# Brickster_8884bt_Receiver.net
KiCad netlist of a schematic drawn in EAGLE
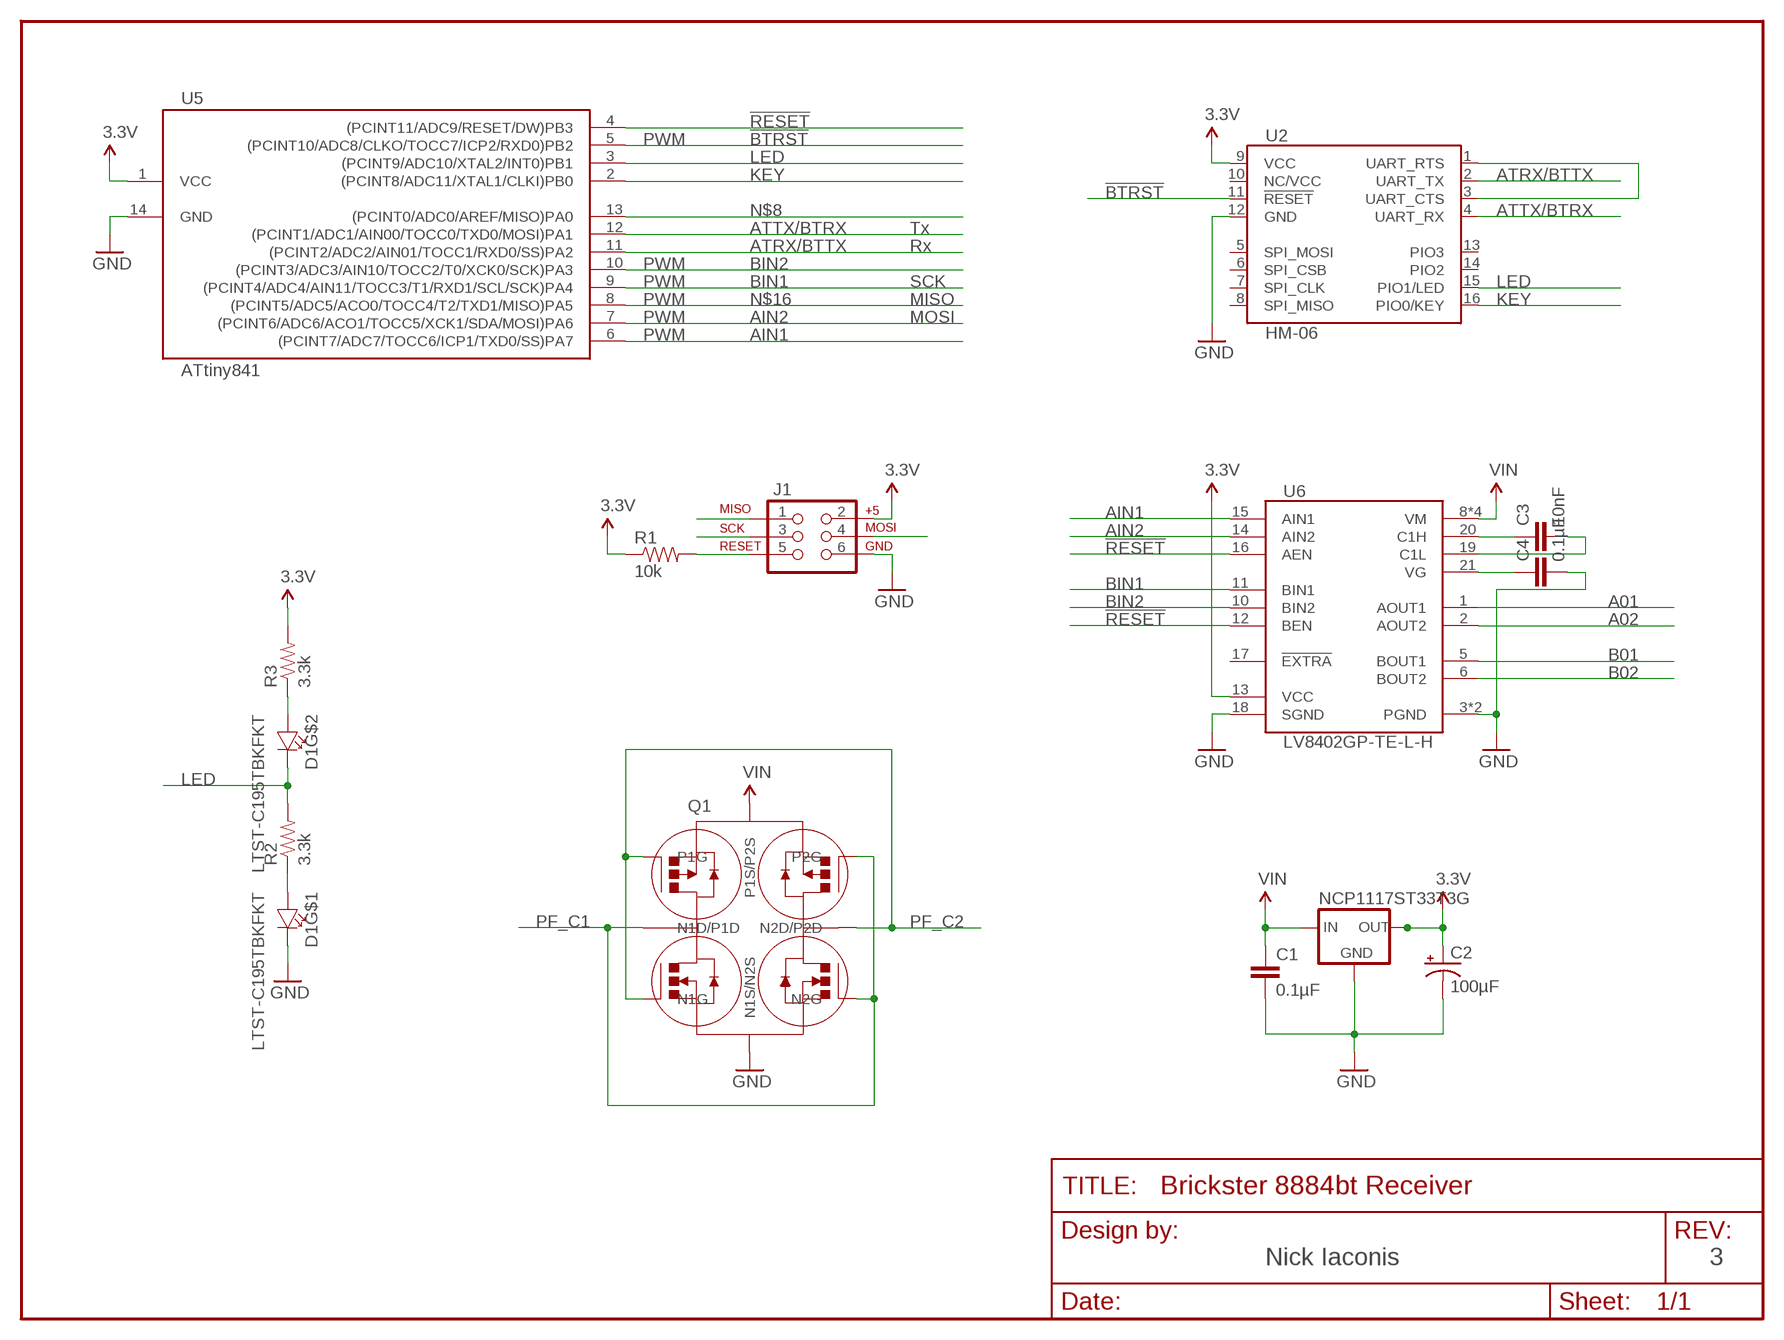
[diagram p0: schematic, sheet 1]

(export (version "E")
  (design (tool "Eeschema 10.0.6"))
  (components
    (comp (ref "C1")
      (value "0.1µF")
      (footprint "eagle-import:0402")
      (libsource (lib "eagle-import") (part "C0402"))
    )
    (comp (ref "C2")
      (value "100µF")
      (footprint "eagle-import:1206")
      (libsource (lib "eagle-import") (part "C_POL"))
    )
    (comp (ref "C3")
      (value "10nF")
      (footprint "eagle-import:0402")
      (libsource (lib "eagle-import") (part "C0402"))
    )
    (comp (ref "C4")
      (value "0.1µF")
      (footprint "eagle-import:0402")
      (libsource (lib "eagle-import") (part "C0402"))
    )
    (comp (ref "D1")
      (value "LTST-C195TBKFKT")
      (footprint "eagle-import:CHIP-LTST")
      (libsource (lib "eagle-import") (part "LED_LTST_C195TBKFKT"))
    )
    (comp (ref "J1")
      (value "AVR_SPI_PRG_6NS")
      (footprint "eagle-import:2X3-NS")
      (libsource (lib "eagle-import") (part "AVR_SPI_PRG_6NS"))
    )
    (comp (ref "NCP1117ST33T3G")
      (value "IC_RT9164A")
      (footprint "eagle-import:SOT223")
      (libsource (lib "eagle-import") (part "IC_RT9164A"))
    )
    (comp (ref "Q1")
      (value "DMHC3025LSD-13")
      (footprint "eagle-import:SO8")
      (libsource (lib "eagle-import") (part "IC_FET_BRIDGESO8"))
    )
    (comp (ref "R1")
      (value "10k")
      (footprint "eagle-import:0402")
      (fields (field (name "PARTNO") "ERJ-3GEYJ103V"))
      (libsource (lib "eagle-import") (part "R0402"))
    )
    (comp (ref "R2")
      (value "3.3k")
      (footprint "eagle-import:0402")
      (fields (field (name "PARTNO") "ERJ-3GEYJ103V"))
      (libsource (lib "eagle-import") (part "R0402"))
    )
    (comp (ref "R3")
      (value "3.3k")
      (footprint "eagle-import:0402")
      (fields (field (name "PARTNO") "ERJ-3GEYJ103V"))
      (libsource (lib "eagle-import") (part "R0402"))
    )
    (comp (ref "U2")
      (value "HM-06")
      (footprint "eagle-import:HM-05_06_07")
      (libsource (lib "eagle-import") (part "HM-05/06/07HM-05/06/07"))
    )
    (comp (ref "U5")
      (value "ATtiny841")
      (footprint "eagle-import:14SOICN")
      (libsource (lib "eagle-import") (part "ATTINY441/841-SSU"))
    )
    (comp (ref "U6")
      (value "LV8402GP-TE-L-H")
      (footprint "eagle-import:VCT24")
      (libsource (lib "eagle-import") (part "LV8402GPLV8402GP"))
    )
  )
  (nets
    (net (code "1") (name "/A01") (class "Default")
      (node (ref "U6") (pin "1") (pinfunction "AOUT1_1") (pintype "bidirectional"))
    )
    (net (code "2") (name "/A02") (class "Default")
      (node (ref "U6") (pin "2") (pinfunction "AOUT2_2") (pintype "bidirectional"))
    )
    (net (code "3") (name "/AIN1") (class "Default")
      (node (ref "U5") (pin "6") (pinfunction "(PCINT7/ADC7/TOCC6/ICP1/TXD0/SS)PA7_6") (pintype "bidirectional"))
      (node (ref "U6") (pin "15") (pinfunction "AIN1_15") (pintype "bidirectional"))
    )
    (net (code "4") (name "/AIN2") (class "Default")
      (node (ref "J1") (pin "4") (pinfunction "4_4") (pintype "passive"))
      (node (ref "U5") (pin "7") (pinfunction "(PCINT6/ADC6/ACO1/TOCC5/XCK1/SDA/MOSI)PA6_7") (pintype "bidirectional"))
      (node (ref "U6") (pin "14") (pinfunction "AIN2_14") (pintype "bidirectional"))
    )
    (net (code "5") (name "/ATRX{slash}BTTX") (class "Default")
      (node (ref "U2") (pin "2") (pinfunction "UART_TX_2") (pintype "bidirectional"))
      (node (ref "U5") (pin "11") (pinfunction "(PCINT2/ADC2/AIN01/TOCC1/RXD0/SS)PA2_11") (pintype "bidirectional"))
    )
    (net (code "6") (name "/ATTX{slash}BTRX") (class "Default")
      (node (ref "U2") (pin "4") (pinfunction "UART_RX_4") (pintype "bidirectional"))
      (node (ref "U5") (pin "12") (pinfunction "(PCINT1/ADC1/AIN00/TOCC0/TXD0/MOSI)PA1_12") (pintype "bidirectional"))
    )
    (net (code "7") (name "/B01") (class "Default")
      (node (ref "U6") (pin "5") (pinfunction "BOUT1_5") (pintype "bidirectional"))
    )
    (net (code "8") (name "/B02") (class "Default")
      (node (ref "U6") (pin "6") (pinfunction "BOUT2_6") (pintype "bidirectional"))
    )
    (net (code "9") (name "/BIN1") (class "Default")
      (node (ref "J1") (pin "3") (pinfunction "3_3") (pintype "passive"))
      (node (ref "U5") (pin "9") (pinfunction "(PCINT4/ADC4/AIN11/TOCC3/T1/RXD1/SCL/SCK)PA4_9") (pintype "bidirectional"))
      (node (ref "U6") (pin "11") (pinfunction "BIN1_11") (pintype "bidirectional"))
    )
    (net (code "10") (name "/BIN2") (class "Default")
      (node (ref "U5") (pin "10") (pinfunction "(PCINT3/ADC3/AIN10/TOCC2/T0/XCK0/SCK)PA3_10") (pintype "bidirectional"))
      (node (ref "U6") (pin "10") (pinfunction "BIN2_10") (pintype "bidirectional"))
    )
    (net (code "11") (name "/KEY") (class "Default")
      (node (ref "U2") (pin "16") (pinfunction "PIO0/KEY_16") (pintype "bidirectional"))
      (node (ref "U5") (pin "2") (pinfunction "(PCINT8/ADC11/XTAL1/CLKI)PB0_2") (pintype "bidirectional"))
    )
    (net (code "12") (name "/LED") (class "Default")
      (node (ref "D1") (pin "4") (pinfunction "P$2_4") (pintype "output"))
      (node (ref "R2") (pin "2") (pinfunction "2_2") (pintype "passive"))
      (node (ref "U2") (pin "15") (pinfunction "PIO1/LED_15") (pintype "bidirectional"))
      (node (ref "U5") (pin "3") (pinfunction "(PCINT9/ADC10/XTAL2/INT0)PB1_3") (pintype "bidirectional"))
    )
    (net (code "13") (name "/N$8") (class "Default")
      (node (ref "U5") (pin "13") (pinfunction "(PCINT0/ADC0/AREF/MISO)PA0_13") (pintype "bidirectional"))
    )
    (net (code "14") (name "/N$16") (class "Default")
      (node (ref "J1") (pin "1") (pinfunction "1_1") (pintype "passive"))
      (node (ref "U5") (pin "8") (pinfunction "(PCINT5/ADC5/ACO0/TOCC4/T2/TXD1/MISO)PA5_8") (pintype "bidirectional"))
    )
    (net (code "15") (name "/PF_C1") (class "Default")
      (node (ref "Q1") (pin "P$2") (pinfunction "N1D/P1D_P$2") (pintype "bidirectional"))
      (node (ref "Q1") (pin "P$4") (pinfunction "N2G_P$4") (pintype "bidirectional"))
      (node (ref "Q1") (pin "P$5") (pinfunction "P2G_P$5") (pintype "bidirectional"))
    )
    (net (code "16") (name "/PF_C2") (class "Default")
      (node (ref "Q1") (pin "P$1") (pinfunction "N1G_P$1") (pintype "bidirectional"))
      (node (ref "Q1") (pin "P$6") (pinfunction "N2D/P2D_P$6") (pintype "bidirectional"))
      (node (ref "Q1") (pin "P$8") (pinfunction "P1G_P$8") (pintype "bidirectional"))
    )
    (net (code "17") (name "/~{BTRST}") (class "Default")
      (node (ref "U2") (pin "11") (pinfunction "~{RESET}_11") (pintype "bidirectional"))
      (node (ref "U5") (pin "5") (pinfunction "(PCINT10/ADC8/CLKO/TOCC7/ICP2/RXD0)PB2_5") (pintype "bidirectional"))
    )
    (net (code "18") (name "/~{RESET}") (class "Default")
      (node (ref "J1") (pin "5") (pinfunction "5_5") (pintype "passive"))
      (node (ref "R1") (pin "2") (pinfunction "2_2") (pintype "passive"))
      (node (ref "U5") (pin "4") (pinfunction "(PCINT11/ADC9/RESET/DW)PB3_4") (pintype "bidirectional"))
      (node (ref "U6") (pin "12") (pinfunction "BEN_12") (pintype "bidirectional"))
      (node (ref "U6") (pin "16") (pinfunction "AEN_16") (pintype "bidirectional"))
    )
    (net (code "19") (name "3.3V") (class "Default")
      (node (ref "C2") (pin "1") (pinfunction "+_1") (pintype "passive"))
      (node (ref "J1") (pin "2") (pinfunction "2_2") (pintype "passive"))
      (node (ref "NCP1117ST33T3G") (pin "2") (pinfunction "OUT_2") (pintype "output"))
      (node (ref "NCP1117ST33T3G") (pin "4") (pinfunction "P$1_4") (pintype "output"))
      (node (ref "R1") (pin "1") (pinfunction "1_1") (pintype "passive"))
      (node (ref "R3") (pin "2") (pinfunction "2_2") (pintype "passive"))
      (node (ref "U2") (pin "9") (pinfunction "VCC_9") (pintype "bidirectional"))
      (node (ref "U5") (pin "1") (pinfunction "VCC_1") (pintype "bidirectional"))
      (node (ref "U6") (pin "13") (pinfunction "VCC_13") (pintype "bidirectional"))
    )
    (net (code "20") (name "GND") (class "Default")
      (node (ref "C1") (pin "2") (pinfunction "2_2") (pintype "passive"))
      (node (ref "C2") (pin "2") (pinfunction "-_2") (pintype "passive"))
      (node (ref "C4") (pin "2") (pinfunction "2_2") (pintype "passive"))
      (node (ref "D1") (pin "3") (pinfunction "P$2_3") (pintype "output"))
      (node (ref "J1") (pin "6") (pinfunction "6_6") (pintype "passive"))
      (node (ref "NCP1117ST33T3G") (pin "1") (pinfunction "GND_1") (pintype "input"))
      (node (ref "Q1") (pin "P$3") (pinfunction "N1S/N2S_P$3") (pintype "bidirectional"))
      (node (ref "U2") (pin "12") (pinfunction "GND_12") (pintype "bidirectional"))
      (node (ref "U5") (pin "14") (pinfunction "GND_14") (pintype "bidirectional"))
      (node (ref "U6") (pin "18") (pinfunction "SGND_18") (pintype "bidirectional"))
      (node (ref "U6") (pin "3") (pinfunction "PGND_3") (pintype "bidirectional"))
      (node (ref "U6") (pin "4") (pinfunction "PGND_4") (pintype "bidirectional"))
    )
    (net (code "21") (name "Net-(D1A-P$1)") (class "Default")
      (node (ref "D1") (pin "1") (pinfunction "P$1_1") (pintype "input"))
      (node (ref "R2") (pin "1") (pinfunction "1_1") (pintype "passive"))
    )
    (net (code "22") (name "Net-(D1B-P$1)") (class "Default")
      (node (ref "D1") (pin "2") (pinfunction "P$1_2") (pintype "input"))
      (node (ref "R3") (pin "1") (pinfunction "1_1") (pintype "passive"))
    )
    (net (code "23") (name "Net-(U2-UART_CTS)") (class "Default")
      (node (ref "U2") (pin "1") (pinfunction "UART_RTS_1") (pintype "bidirectional"))
      (node (ref "U2") (pin "3") (pinfunction "UART_CTS_3") (pintype "bidirectional"))
    )
    (net (code "24") (name "Net-(U6-C1H)") (class "Default")
      (node (ref "C3") (pin "1") (pinfunction "1_1") (pintype "passive"))
      (node (ref "U6") (pin "20") (pinfunction "C1H_20") (pintype "bidirectional"))
    )
    (net (code "25") (name "Net-(U6-C1L)") (class "Default")
      (node (ref "C3") (pin "2") (pinfunction "2_2") (pintype "passive"))
      (node (ref "U6") (pin "19") (pinfunction "C1L_19") (pintype "bidirectional"))
    )
    (net (code "26") (name "Net-(U6-VG)") (class "Default")
      (node (ref "C4") (pin "1") (pinfunction "1_1") (pintype "passive"))
      (node (ref "U6") (pin "21") (pinfunction "VG_21") (pintype "bidirectional"))
    )
    (net (code "27") (name "VIN") (class "Default")
      (node (ref "C1") (pin "1") (pinfunction "1_1") (pintype "passive"))
      (node (ref "NCP1117ST33T3G") (pin "3") (pinfunction "IN_3") (pintype "input"))
      (node (ref "Q1") (pin "P$7") (pinfunction "P1S/P2S_P$7") (pintype "bidirectional"))
      (node (ref "U6") (pin "22") (pinfunction "VM_22") (pintype "bidirectional"))
      (node (ref "U6") (pin "23") (pinfunction "VM_23") (pintype "bidirectional"))
      (node (ref "U6") (pin "8") (pinfunction "VM_8") (pintype "bidirectional"))
      (node (ref "U6") (pin "9") (pinfunction "VM_9") (pintype "bidirectional"))
    )
    (net (code "28") (name "unconnected-(U2-NC{slash}VCC-Pad10)") (class "Default")
      (node (ref "U2") (pin "10") (pinfunction "NC/VCC_10") (pintype "bidirectional"))
    )
    (net (code "29") (name "unconnected-(U2-PIO2-Pad14)") (class "Default")
      (node (ref "U2") (pin "14") (pinfunction "PIO2_14") (pintype "bidirectional"))
    )
    (net (code "30") (name "unconnected-(U2-PIO3-Pad13)") (class "Default")
      (node (ref "U2") (pin "13") (pinfunction "PIO3_13") (pintype "bidirectional"))
    )
    (net (code "31") (name "unconnected-(U2-SPI_CLK-Pad7)") (class "Default")
      (node (ref "U2") (pin "7") (pinfunction "SPI_CLK_7") (pintype "bidirectional"))
    )
    (net (code "32") (name "unconnected-(U2-SPI_CSB-Pad6)") (class "Default")
      (node (ref "U2") (pin "6") (pinfunction "SPI_CSB_6") (pintype "bidirectional"))
    )
    (net (code "33") (name "unconnected-(U2-SPI_MISO-Pad8)") (class "Default")
      (node (ref "U2") (pin "8") (pinfunction "SPI_MISO_8") (pintype "bidirectional"))
    )
    (net (code "34") (name "unconnected-(U2-SPI_MOSI-Pad5)") (class "Default")
      (node (ref "U2") (pin "5") (pinfunction "SPI_MOSI_5") (pintype "bidirectional"))
    )
    (net (code "35") (name "unconnected-(U6-~{EXTRA}-Pad17)") (class "Default")
      (node (ref "U6") (pin "17") (pinfunction "~{EXTRA}_17") (pintype "bidirectional"))
    )
  )
)
